# relay_pi_interface.net
KiCad netlist of a schematic drawn in Altium Designer
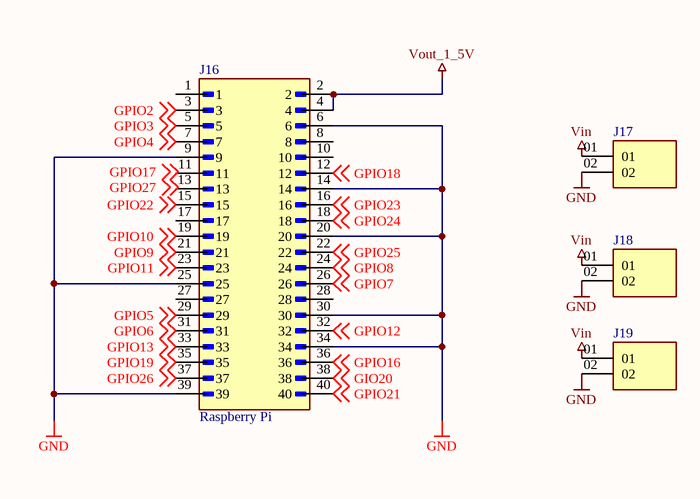
[diagram p0: relay_pi_interface.SchDoc]

(export (version "E")
  (design (tool "Eeschema 10.0.6"))
  (components
    (comp (ref "J16")
      (value "Raspberry Pi")
      (footprint "MODULE_RASPBERRY_PI_3_MODEL_B+")
      (description "Connector Header Through Hole, Right Angle 40 position 0.100 (2.54mm)")
      (fields (field (name "MF") "Sullins Connector") (field (name "MP") "SBH11-PBPC-D20-RA-BK"))
      (libsource (lib "SBH11-PBPC-D20-RA-BK") (part "SBH11-PBPC-D20-RA-BK"))
    )
    (comp (ref "J17")
      (value "BBS-102-T-A")
      (footprint "SAMTEC_BBS-102-T-A")
      (fields (field (name "MF") "Samtec") (field (name "MP") "BBS102TA"))
      (libsource (lib "BBS-102-T-A") (part "BBS-102-T-A"))
    )
    (comp (ref "J18")
      (value "BBS-102-T-A")
      (footprint "SAMTEC_BBS-102-T-A")
      (fields (field (name "MF") "Samtec") (field (name "MP") "BBS102TA"))
      (libsource (lib "BBS-102-T-A") (part "BBS-102-T-A"))
    )
    (comp (ref "J19")
      (value "BBS-102-T-A")
      (footprint "SAMTEC_BBS-102-T-A")
      (fields (field (name "MF") "Samtec") (field (name "MP") "BBS102TA"))
      (libsource (lib "BBS-102-T-A") (part "BBS-102-T-A"))
    )
  )
  (nets
    (net (code "1") (name "GIO20") (class "Default")
      (node (ref "J16") (pin "38") (pinfunction "38_38") (pintype "passive"))
    )
    (net (code "2") (name "GND") (class "Default")
      (node (ref "J16") (pin "14") (pinfunction "14_14") (pintype "passive"))
      (node (ref "J16") (pin "20") (pinfunction "20_20") (pintype "passive"))
      (node (ref "J16") (pin "25") (pinfunction "25_25") (pintype "passive"))
      (node (ref "J16") (pin "30") (pinfunction "30_30") (pintype "passive"))
      (node (ref "J16") (pin "34") (pinfunction "34_34") (pintype "passive"))
      (node (ref "J16") (pin "39") (pinfunction "39_39") (pintype "passive"))
      (node (ref "J16") (pin "6") (pinfunction "6_6") (pintype "passive"))
      (node (ref "J16") (pin "9") (pinfunction "9_9") (pintype "passive"))
      (node (ref "J17") (pin "02") (pinfunction "02_02") (pintype "passive"))
      (node (ref "J18") (pin "02") (pinfunction "02_02") (pintype "passive"))
      (node (ref "J19") (pin "02") (pinfunction "02_02") (pintype "passive"))
    )
    (net (code "3") (name "GPIO2") (class "Default")
      (node (ref "J16") (pin "3") (pinfunction "3_3") (pintype "passive"))
    )
    (net (code "4") (name "GPIO3") (class "Default")
      (node (ref "J16") (pin "5") (pinfunction "5_5") (pintype "passive"))
    )
    (net (code "5") (name "GPIO4") (class "Default")
      (node (ref "J16") (pin "7") (pinfunction "7_7") (pintype "passive"))
    )
    (net (code "6") (name "GPIO5") (class "Default")
      (node (ref "J16") (pin "29") (pinfunction "29_29") (pintype "passive"))
    )
    (net (code "7") (name "GPIO6") (class "Default")
      (node (ref "J16") (pin "31") (pinfunction "31_31") (pintype "passive"))
    )
    (net (code "8") (name "GPIO7") (class "Default")
      (node (ref "J16") (pin "26") (pinfunction "26_26") (pintype "passive"))
    )
    (net (code "9") (name "GPIO8") (class "Default")
      (node (ref "J16") (pin "24") (pinfunction "24_24") (pintype "passive"))
    )
    (net (code "10") (name "GPIO9") (class "Default")
      (node (ref "J16") (pin "21") (pinfunction "21_21") (pintype "passive"))
    )
    (net (code "11") (name "GPIO10") (class "Default")
      (node (ref "J16") (pin "19") (pinfunction "19_19") (pintype "passive"))
    )
    (net (code "12") (name "GPIO11") (class "Default")
      (node (ref "J16") (pin "23") (pinfunction "23_23") (pintype "passive"))
    )
    (net (code "13") (name "GPIO12") (class "Default")
      (node (ref "J16") (pin "32") (pinfunction "32_32") (pintype "passive"))
    )
    (net (code "14") (name "GPIO13") (class "Default")
      (node (ref "J16") (pin "33") (pinfunction "33_33") (pintype "passive"))
    )
    (net (code "15") (name "GPIO16") (class "Default")
      (node (ref "J16") (pin "36") (pinfunction "36_36") (pintype "passive"))
    )
    (net (code "17") (name "GPIO18") (class "Default")
      (node (ref "J16") (pin "12") (pinfunction "12_12") (pintype "passive"))
    )
    (net (code "18") (name "GPIO19") (class "Default")
      (node (ref "J16") (pin "35") (pinfunction "35_35") (pintype "passive"))
    )
    (net (code "19") (name "GPIO21") (class "Default")
      (node (ref "J16") (pin "40") (pinfunction "40_40") (pintype "passive"))
    )
    (net (code "20") (name "GPIO22") (class "Default")
      (node (ref "J16") (pin "15") (pinfunction "15_15") (pintype "passive"))
    )
    (net (code "21") (name "GPIO23") (class "Default")
      (node (ref "J16") (pin "16") (pinfunction "16_16") (pintype "passive"))
    )
    (net (code "22") (name "GPIO24") (class "Default")
      (node (ref "J16") (pin "18") (pinfunction "18_18") (pintype "passive"))
    )
    (net (code "23") (name "GPIO25") (class "Default")
      (node (ref "J16") (pin "22") (pinfunction "22_22") (pintype "passive"))
    )
    (net (code "24") (name "GPIO26") (class "Default")
      (node (ref "J16") (pin "37") (pinfunction "37_37") (pintype "passive"))
    )
    (net (code "26") (name "Vin") (class "Default")
      (node (ref "J17") (pin "01") (pinfunction "01_01") (pintype "passive"))
      (node (ref "J18") (pin "01") (pinfunction "01_01") (pintype "passive"))
      (node (ref "J19") (pin "01") (pinfunction "01_01") (pintype "passive"))
    )
    (net (code "27") (name "Vout_1_5V") (class "Default")
      (node (ref "J16") (pin "2") (pinfunction "2_2") (pintype "passive"))
      (node (ref "J16") (pin "4") (pinfunction "4_4") (pintype "passive"))
    )
    (net (code "28") (name "unconnected-(J16-Pad1)") (class "Default")
      (node (ref "J16") (pin "1") (pinfunction "1_1") (pintype "passive"))
    )
    (net (code "29") (name "unconnected-(J16-Pad8)") (class "Default")
      (node (ref "J16") (pin "8") (pinfunction "8_8") (pintype "passive"))
    )
    (net (code "30") (name "unconnected-(J16-Pad10)") (class "Default")
      (node (ref "J16") (pin "10") (pinfunction "10_10") (pintype "passive"))
    )
    (net (code "31") (name "unconnected-(J16-Pad11)") (class "Default")
      (node (ref "J16") (pin "11") (pinfunction "11_11") (pintype "passive"))
    )
    (net (code "32") (name "unconnected-(J16-Pad13)") (class "Default")
      (node (ref "J16") (pin "13") (pinfunction "13_13") (pintype "passive"))
    )
    (net (code "33") (name "unconnected-(J16-Pad17)") (class "Default")
      (node (ref "J16") (pin "17") (pinfunction "17_17") (pintype "passive"))
    )
    (net (code "34") (name "unconnected-(J16-Pad27)") (class "Default")
      (node (ref "J16") (pin "27") (pinfunction "27_27") (pintype "passive"))
    )
    (net (code "35") (name "unconnected-(J16-Pad28)") (class "Default")
      (node (ref "J16") (pin "28") (pinfunction "28_28") (pintype "passive"))
    )
  )
)
